# LCD.net
KiCad netlist of a schematic drawn in Altium Designer
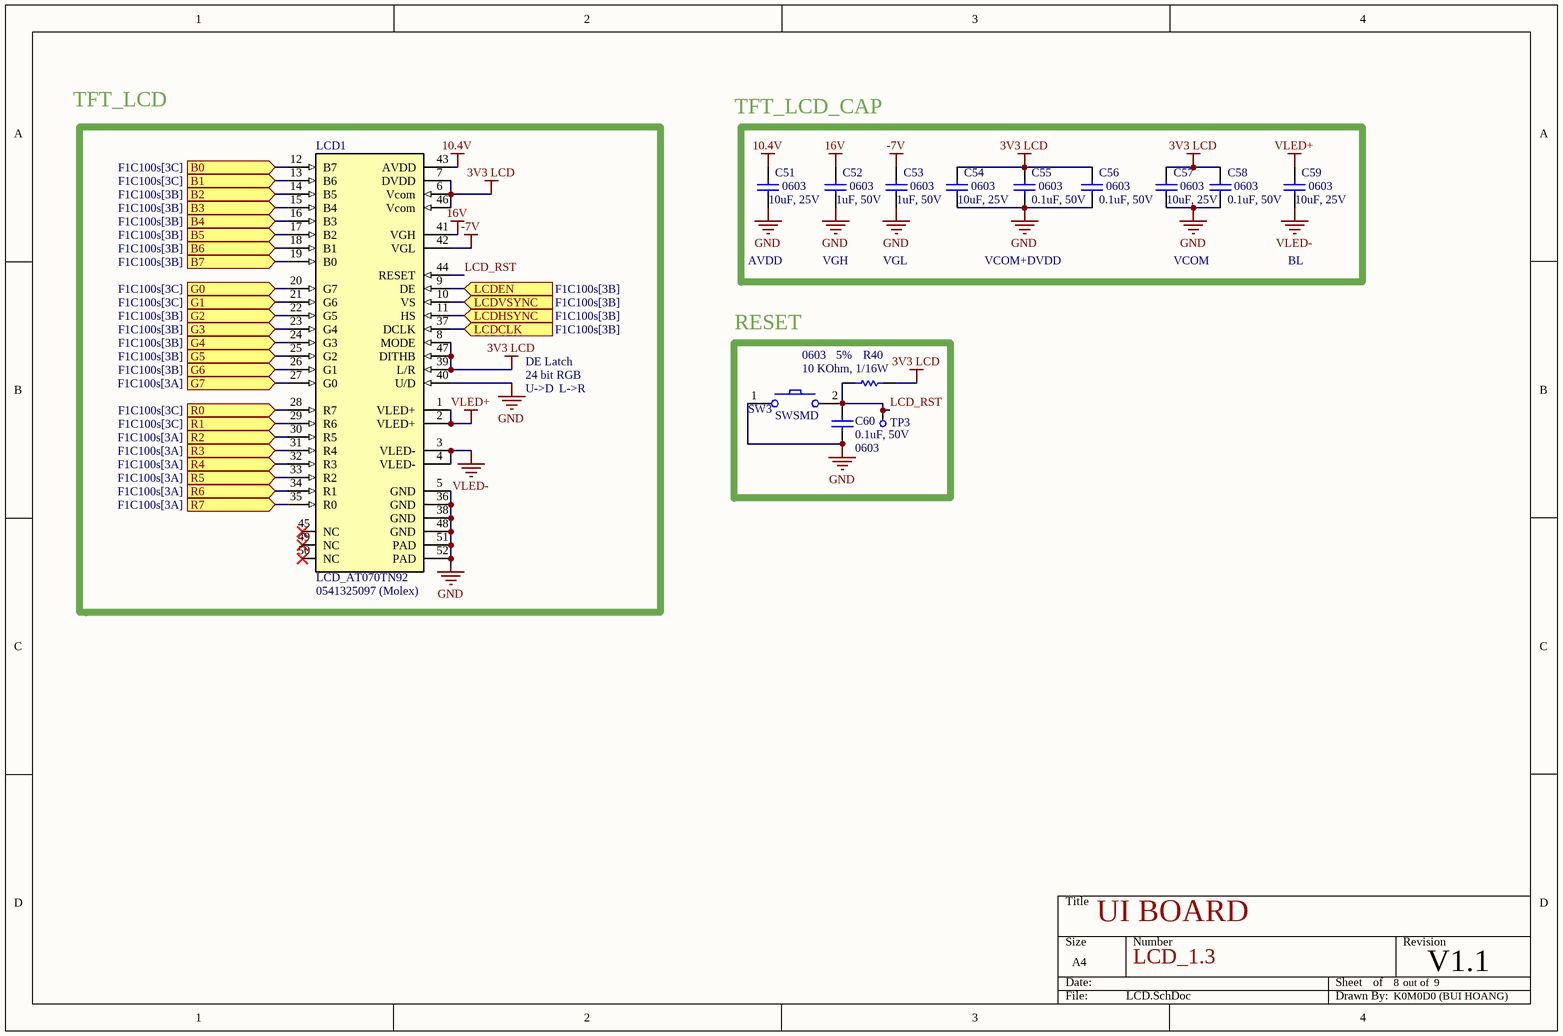
[diagram p0: LCD.SchDoc]

(export (version "E")
  (design (tool "Eeschema 10.0.6"))
  (components
    (comp (ref "C51")
      (value "10uF, 25V")
      (footprint "C_0603")
      (description "CAP_0603")
      (fields (field (name "PACKAGE") "0603"))
      (libsource (lib "DisplayLib") (part "CAP_0603"))
    )
    (comp (ref "C52")
      (value "1uF, 50V")
      (footprint "C_0603")
      (description "CAP_0603")
      (fields (field (name "PACKAGE") "0603"))
      (libsource (lib "DisplayLib") (part "CAP_0603"))
    )
    (comp (ref "C53")
      (value "1uF, 50V")
      (footprint "C_0603")
      (description "CAP_0603")
      (fields (field (name "PACKAGE") "0603"))
      (libsource (lib "DisplayLib") (part "CAP_0603"))
    )
    (comp (ref "C54")
      (value "10uF, 25V")
      (footprint "C_0603")
      (description "CAP_0603")
      (fields (field (name "PACKAGE") "0603"))
      (libsource (lib "DisplayLib") (part "CAP_0603"))
    )
    (comp (ref "C55")
      (value "0.1uF, 50V")
      (footprint "C_0603")
      (description "CAP_0603")
      (fields (field (name "PACKAGE") "0603"))
      (libsource (lib "DisplayLib") (part "CAP_0603"))
    )
    (comp (ref "C56")
      (value "0.1uF, 50V")
      (footprint "C_0603")
      (description "CAP_0603")
      (fields (field (name "PACKAGE") "0603"))
      (libsource (lib "DisplayLib") (part "CAP_0603"))
    )
    (comp (ref "C57")
      (value "10uF, 25V")
      (footprint "C_0603")
      (description "CAP_0603")
      (fields (field (name "PACKAGE") "0603"))
      (libsource (lib "DisplayLib") (part "CAP_0603"))
    )
    (comp (ref "C58")
      (value "0.1uF, 50V")
      (footprint "C_0603")
      (description "CAP_0603")
      (fields (field (name "PACKAGE") "0603"))
      (libsource (lib "DisplayLib") (part "CAP_0603"))
    )
    (comp (ref "C59")
      (value "10uF, 25V")
      (footprint "C_0603")
      (description "CAP_0603")
      (fields (field (name "PACKAGE") "0603"))
      (libsource (lib "DisplayLib") (part "CAP_0603"))
    )
    (comp (ref "C60")
      (value "0.1uF, 50V")
      (footprint "C_0603")
      (description "CAP_0603")
      (fields (field (name "PACKAGE") "0603"))
      (libsource (lib "DisplayLib") (part "CAP_0603"))
    )
    (comp (ref "LCD1")
      (value "LCD_AT070TN92")
      (footprint "CONN_LCD_AT070TN90_NON_ON_PCB")
      (description "LCD 7 inch (800 x 3(RGB) x 480) RES\r\n__NOTE THAT THIS IS FFC 50PINS CONN w/ THE LCD FOOTPRINT!__")
      (fields (field (name "CONNECTOR PART NUMBER") "0541325097 (Molex)"))
      (libsource (lib "DisplayLib") (part "LCD_AT070TN92"))
    )
    (comp (ref "R40")
      (value "10 KOhm, 1/16W")
      (footprint "R_0603")
      (description "RES_0603")
      (fields (field (name "PACKAGE") "0603") (field (name "ACC") "5%"))
      (libsource (lib "DisplayLib") (part "RES_0603"))
    )
    (comp (ref "SW3")
      (value "SWSMD")
      (footprint "SW_SMD_NOGND")
      (description "SW_SMD")
      (libsource (lib "DisplayLib") (part "SWSMD_NOGND"))
    )
    (comp (ref "TP3")
      (value "TESTPT")
      (footprint "TESTPT")
      (description "Test point")
      (libsource (lib "DisplayLib") (part "TESTPT"))
    )
  )
  (nets
    (net (code "1") (name "-7V") (class "Default")
      (node (ref "C53") (pin "2") (pinfunction "2_2") (pintype "passive"))
      (node (ref "LCD1") (pin "42") (pinfunction "VGL_42") (pintype "power_in"))
    )
    (net (code "2") (name "/B0") (class "Default")
      (node (ref "LCD1") (pin "12") (pinfunction "B7_12") (pintype "input"))
    )
    (net (code "3") (name "/B1") (class "Default")
      (node (ref "LCD1") (pin "13") (pinfunction "B6_13") (pintype "input"))
    )
    (net (code "4") (name "/B2") (class "Default")
      (node (ref "LCD1") (pin "14") (pinfunction "B5_14") (pintype "input"))
    )
    (net (code "5") (name "/B3") (class "Default")
      (node (ref "LCD1") (pin "15") (pinfunction "B4_15") (pintype "input"))
    )
    (net (code "6") (name "/B4") (class "Default")
      (node (ref "LCD1") (pin "16") (pinfunction "B3_16") (pintype "input"))
    )
    (net (code "7") (name "/B5") (class "Default")
      (node (ref "LCD1") (pin "17") (pinfunction "B2_17") (pintype "input"))
    )
    (net (code "8") (name "/B6") (class "Default")
      (node (ref "LCD1") (pin "18") (pinfunction "B1_18") (pintype "input"))
    )
    (net (code "9") (name "/B7") (class "Default")
      (node (ref "LCD1") (pin "19") (pinfunction "B0_19") (pintype "input"))
    )
    (net (code "10") (name "/G0") (class "Default")
      (node (ref "LCD1") (pin "20") (pinfunction "G7_20") (pintype "input"))
    )
    (net (code "11") (name "/G1") (class "Default")
      (node (ref "LCD1") (pin "21") (pinfunction "G6_21") (pintype "input"))
    )
    (net (code "12") (name "/G2") (class "Default")
      (node (ref "LCD1") (pin "22") (pinfunction "G5_22") (pintype "input"))
    )
    (net (code "13") (name "/G3") (class "Default")
      (node (ref "LCD1") (pin "23") (pinfunction "G4_23") (pintype "input"))
    )
    (net (code "14") (name "/G4") (class "Default")
      (node (ref "LCD1") (pin "24") (pinfunction "G3_24") (pintype "input"))
    )
    (net (code "15") (name "/G5") (class "Default")
      (node (ref "LCD1") (pin "25") (pinfunction "G2_25") (pintype "input"))
    )
    (net (code "16") (name "/G6") (class "Default")
      (node (ref "LCD1") (pin "26") (pinfunction "G1_26") (pintype "input"))
    )
    (net (code "17") (name "/G7") (class "Default")
      (node (ref "LCD1") (pin "27") (pinfunction "G0_27") (pintype "input"))
    )
    (net (code "18") (name "/LCDCLK") (class "Default")
      (node (ref "LCD1") (pin "37") (pinfunction "DCLK_37") (pintype "input"))
    )
    (net (code "19") (name "/LCDEN") (class "Default")
      (node (ref "LCD1") (pin "9") (pinfunction "DE_9") (pintype "input"))
    )
    (net (code "20") (name "/LCDHSYNC") (class "Default")
      (node (ref "LCD1") (pin "11") (pinfunction "HS_11") (pintype "input"))
    )
    (net (code "21") (name "/LCDVSYNC") (class "Default")
      (node (ref "LCD1") (pin "10") (pinfunction "VS_10") (pintype "input"))
    )
    (net (code "22") (name "/LCD_RST") (class "Default")
      (node (ref "C60") (pin "2") (pinfunction "2_2") (pintype "passive"))
      (node (ref "LCD1") (pin "44") (pinfunction "RESET_44") (pintype "input"))
      (node (ref "R40") (pin "1") (pinfunction "1_1") (pintype "passive"))
      (node (ref "SW3") (pin "2") (pinfunction "2_2") (pintype "passive"))
      (node (ref "TP3") (pin "1") (pinfunction "1_1") (pintype "passive"))
    )
    (net (code "23") (name "/R0") (class "Default")
      (node (ref "LCD1") (pin "28") (pinfunction "R7_28") (pintype "input"))
    )
    (net (code "24") (name "/R1") (class "Default")
      (node (ref "LCD1") (pin "29") (pinfunction "R6_29") (pintype "input"))
    )
    (net (code "25") (name "/R2") (class "Default")
      (node (ref "LCD1") (pin "30") (pinfunction "R5_30") (pintype "input"))
    )
    (net (code "26") (name "/R3") (class "Default")
      (node (ref "LCD1") (pin "31") (pinfunction "R4_31") (pintype "input"))
    )
    (net (code "27") (name "/R4") (class "Default")
      (node (ref "LCD1") (pin "32") (pinfunction "R3_32") (pintype "input"))
    )
    (net (code "28") (name "/R5") (class "Default")
      (node (ref "LCD1") (pin "33") (pinfunction "R2_33") (pintype "input"))
    )
    (net (code "29") (name "/R6") (class "Default")
      (node (ref "LCD1") (pin "34") (pinfunction "R1_34") (pintype "input"))
    )
    (net (code "30") (name "/R7") (class "Default")
      (node (ref "LCD1") (pin "35") (pinfunction "R0_35") (pintype "input"))
    )
    (net (code "31") (name "3V3 LCD") (class "Default")
      (node (ref "C54") (pin "2") (pinfunction "2_2") (pintype "passive"))
      (node (ref "C55") (pin "2") (pinfunction "2_2") (pintype "passive"))
      (node (ref "C56") (pin "2") (pinfunction "2_2") (pintype "passive"))
      (node (ref "C57") (pin "2") (pinfunction "2_2") (pintype "passive"))
      (node (ref "C58") (pin "2") (pinfunction "2_2") (pintype "passive"))
      (node (ref "LCD1") (pin "39") (pinfunction "L/R_39") (pintype "input"))
      (node (ref "LCD1") (pin "46") (pinfunction "Vcom_46") (pintype "input"))
      (node (ref "LCD1") (pin "47") (pinfunction "DITHB_47") (pintype "input"))
      (node (ref "LCD1") (pin "6") (pinfunction "Vcom_6") (pintype "input"))
      (node (ref "LCD1") (pin "7") (pinfunction "DVDD_7") (pintype "power_in"))
      (node (ref "LCD1") (pin "8") (pinfunction "MODE_8") (pintype "input"))
      (node (ref "R40") (pin "2") (pinfunction "2_2") (pintype "passive"))
    )
    (net (code "32") (name "10.4V") (class "Default")
      (node (ref "C51") (pin "2") (pinfunction "2_2") (pintype "passive"))
      (node (ref "LCD1") (pin "43") (pinfunction "AVDD_43") (pintype "power_in"))
    )
    (net (code "33") (name "16V") (class "Default")
      (node (ref "C52") (pin "2") (pinfunction "2_2") (pintype "passive"))
      (node (ref "LCD1") (pin "41") (pinfunction "VGH_41") (pintype "power_in"))
    )
    (net (code "34") (name "GND") (class "Default")
      (node (ref "C51") (pin "1") (pinfunction "1_1") (pintype "passive"))
      (node (ref "C52") (pin "1") (pinfunction "1_1") (pintype "passive"))
      (node (ref "C53") (pin "1") (pinfunction "1_1") (pintype "passive"))
      (node (ref "C54") (pin "1") (pinfunction "1_1") (pintype "passive"))
      (node (ref "C55") (pin "1") (pinfunction "1_1") (pintype "passive"))
      (node (ref "C56") (pin "1") (pinfunction "1_1") (pintype "passive"))
      (node (ref "C57") (pin "1") (pinfunction "1_1") (pintype "passive"))
      (node (ref "C58") (pin "1") (pinfunction "1_1") (pintype "passive"))
      (node (ref "C60") (pin "1") (pinfunction "1_1") (pintype "passive"))
      (node (ref "LCD1") (pin "36") (pinfunction "GND_36") (pintype "power_in"))
      (node (ref "LCD1") (pin "38") (pinfunction "GND_38") (pintype "power_in"))
      (node (ref "LCD1") (pin "40") (pinfunction "U/D_40") (pintype "input"))
      (node (ref "LCD1") (pin "48") (pinfunction "GND_48") (pintype "power_in"))
      (node (ref "LCD1") (pin "5") (pinfunction "GND_5") (pintype "power_in"))
      (node (ref "LCD1") (pin "51") (pinfunction "PAD_51") (pintype "power_in"))
      (node (ref "LCD1") (pin "52") (pinfunction "PAD_52") (pintype "power_in"))
      (node (ref "SW3") (pin "1") (pinfunction "1_1") (pintype "passive"))
    )
    (net (code "35") (name "VLED+") (class "Default")
      (node (ref "C59") (pin "2") (pinfunction "2_2") (pintype "passive"))
      (node (ref "LCD1") (pin "1") (pinfunction "VLED+_1") (pintype "power_in"))
      (node (ref "LCD1") (pin "2") (pinfunction "VLED+_2") (pintype "power_in"))
    )
    (net (code "36") (name "VLED-") (class "Default")
      (node (ref "C59") (pin "1") (pinfunction "1_1") (pintype "passive"))
      (node (ref "LCD1") (pin "3") (pinfunction "VLED-_3") (pintype "power_in"))
      (node (ref "LCD1") (pin "4") (pinfunction "VLED-_4") (pintype "power_in"))
    )
    (net (code "37") (name "unconnected-(LCD1-NC-Pad45)") (class "Default")
      (node (ref "LCD1") (pin "45") (pinfunction "NC_45") (pintype "passive+no_connect"))
    )
    (net (code "38") (name "unconnected-(LCD1-NC-Pad49)") (class "Default")
      (node (ref "LCD1") (pin "49") (pinfunction "NC_49") (pintype "passive+no_connect"))
    )
    (net (code "39") (name "unconnected-(LCD1-NC-Pad50)") (class "Default")
      (node (ref "LCD1") (pin "50") (pinfunction "NC_50") (pintype "passive+no_connect"))
    )
  )
)
